# hexbot.net
KiCad netlist of a schematic drawn in Altium Designer
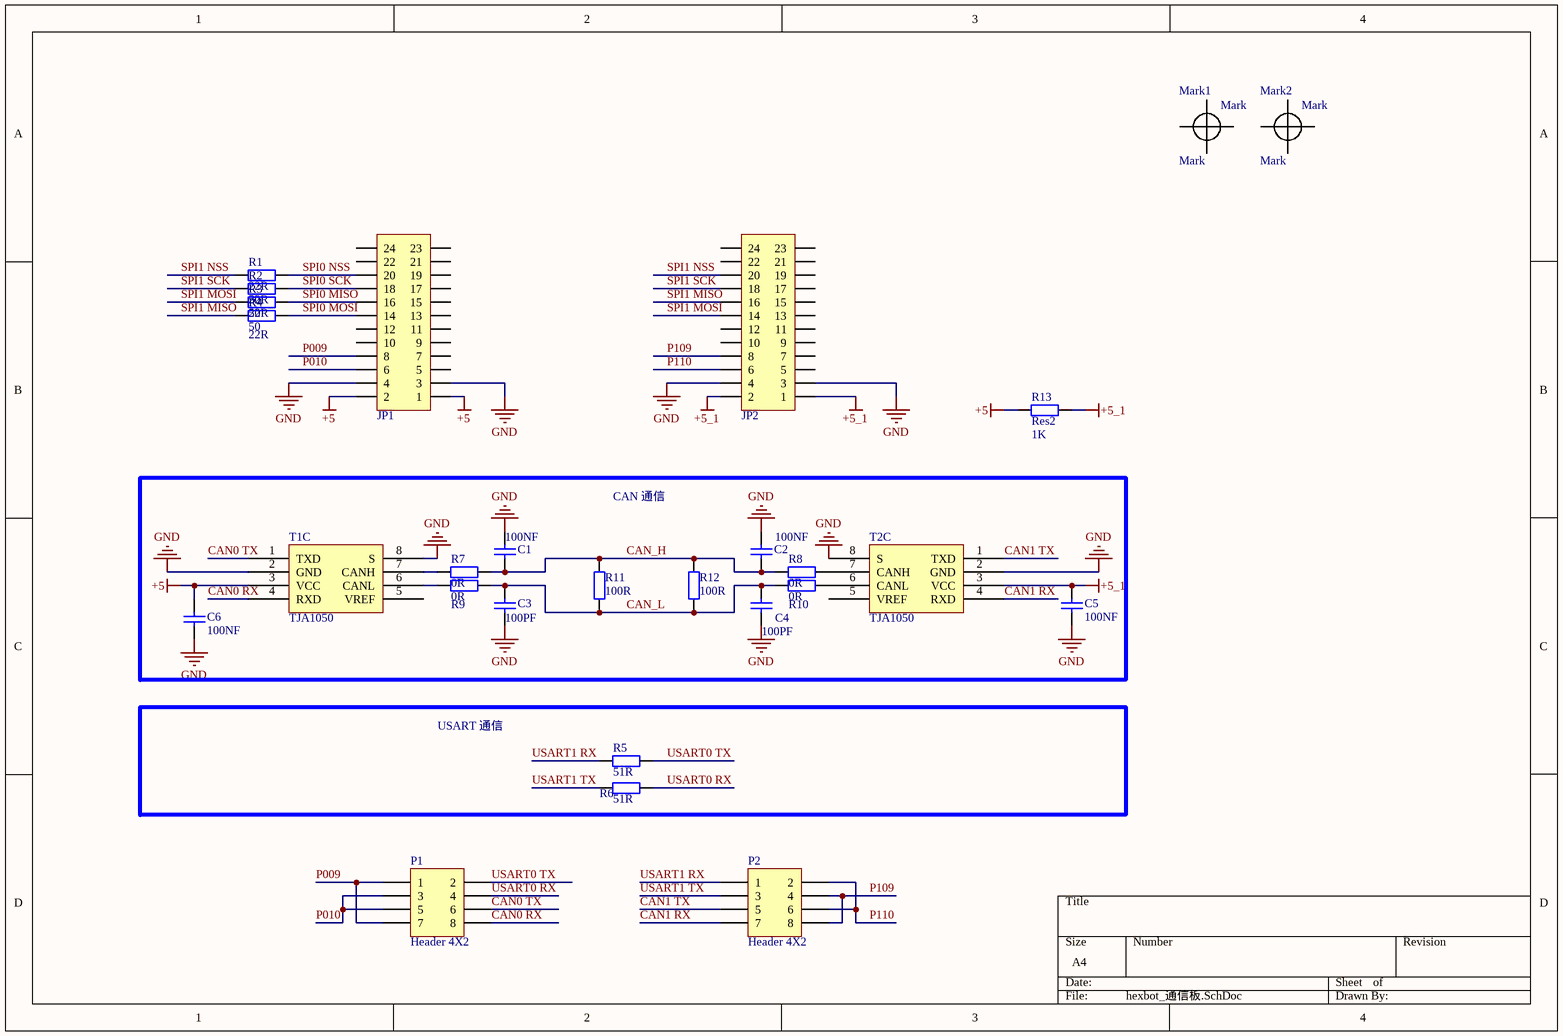
[diagram p0: hexbot_通信板.SchDoc]

(export (version "E")
  (design (tool "Eeschema 10.0.6"))
  (components
    (comp (ref "C1")
      (value "100NF")
      (footprint "1608[0603]")
      (description "Capacitor")
      (fields (field (name "PUBLISHER") "Altium Limited"))
      (libsource (lib "Miscellaneous Devices") (part "Cap"))
    )
    (comp (ref "C2")
      (value "100NF")
      (footprint "1608[0603]")
      (description "Capacitor")
      (fields (field (name "PUBLISHER") "Altium Limited"))
      (libsource (lib "Miscellaneous Devices") (part "Cap"))
    )
    (comp (ref "C3")
      (value "100PF")
      (footprint "1608[0603]")
      (description "Capacitor")
      (fields (field (name "PUBLISHER") "Altium Limited"))
      (libsource (lib "Miscellaneous Devices") (part "Cap"))
    )
    (comp (ref "C4")
      (value "100PF")
      (footprint "1608[0603]")
      (description "Capacitor")
      (fields (field (name "PUBLISHER") "Altium Limited"))
      (libsource (lib "Miscellaneous Devices") (part "Cap"))
    )
    (comp (ref "C5")
      (value "100NF")
      (footprint "1608[0603]")
      (description "Capacitor")
      (fields (field (name "PUBLISHER") "Altium Limited"))
      (libsource (lib "Miscellaneous Devices") (part "Cap"))
    )
    (comp (ref "C6")
      (value "100NF")
      (footprint "1608[0603]")
      (description "Capacitor")
      (fields (field (name "PUBLISHER") "Altium Limited"))
      (libsource (lib "Miscellaneous Devices") (part "Cap"))
    )
    (comp (ref "JP1")
      (value "Header 2X11")
      (footprint "HDR2.54-WI-2x12P")
      (description "12*2P接插件")
      (fields (field (name "版权归属") "封装库来自淘宝卖家 ID：黄晶宝石"))
      (libsource (lib "5.4 - 接插件-脚距2.54 (100mil) ") (part "Header 12X2"))
    )
    (comp (ref "JP2")
      (value "Header 2X11")
      (footprint "HDR2.54-WI-2x12P")
      (description "12*2P接插件")
      (fields (field (name "版权归属") "封装库来自淘宝卖家 ID：黄晶宝石"))
      (libsource (lib "5.4 - 接插件-脚距2.54 (100mil) ") (part "Header 12X2"))
    )
    (comp (ref "Mark1") (value "Mark") (footprint "Mark:Mark") (libsource (lib "Mark") (part "Mark")))
    (comp (ref "Mark2") (value "Mark") (footprint "Mark:Mark") (libsource (lib "Mark") (part "Mark")))
    (comp (ref "P1")
      (value "Header 4X2")
      (footprint "HDR2X4")
      (description "Header, 4-Pin, Dual row")
      (fields (field (name "PUBLISHER") "Altium Limited"))
      (libsource (lib "Miscellaneous Connectors") (part "Header 4X2"))
    )
    (comp (ref "P2")
      (value "Header 4X2")
      (footprint "HDR2X4")
      (description "Header, 4-Pin, Dual row")
      (fields (field (name "PUBLISHER") "Altium Limited"))
      (libsource (lib "Miscellaneous Connectors") (part "Header 4X2"))
    )
    (comp (ref "R1")
      (value "22R")
      (footprint "1608[0603]")
      (description "Resistor")
      (fields (field (name "ALTIUM_VALUE") "50") (field (name "PUBLISHER") "Altium Limited"))
      (libsource (lib "Miscellaneous Devices") (part "Res2"))
    )
    (comp (ref "R2")
      (value "22R")
      (footprint "1608[0603]")
      (description "Resistor")
      (fields (field (name "ALTIUM_VALUE") "50") (field (name "PUBLISHER") "Altium Limited"))
      (libsource (lib "Miscellaneous Devices") (part "Res2"))
    )
    (comp (ref "R3")
      (value "22R")
      (footprint "1608[0603]")
      (description "Resistor")
      (fields (field (name "ALTIUM_VALUE") "50") (field (name "PUBLISHER") "Altium Limited"))
      (libsource (lib "Miscellaneous Devices") (part "Res2"))
    )
    (comp (ref "R4")
      (value "22R")
      (footprint "1608[0603]")
      (description "Resistor")
      (fields (field (name "PUBLISHER") "Altium Limited"))
      (libsource (lib "Miscellaneous Devices") (part "Res2"))
    )
    (comp (ref "R5")
      (value "51R")
      (footprint "1608[0603]")
      (description "Resistor")
      (fields (field (name "PUBLISHER") "Altium Limited"))
      (libsource (lib "Miscellaneous Devices") (part "Res2"))
    )
    (comp (ref "R6")
      (value "51R")
      (footprint "1608[0603]")
      (description "Resistor")
      (fields (field (name "PUBLISHER") "Altium Limited"))
      (libsource (lib "Miscellaneous Devices") (part "Res2"))
    )
    (comp (ref "R7")
      (value "0R")
      (footprint "1608[0603]")
      (description "Resistor")
      (fields (field (name "PUBLISHER") "Altium Limited"))
      (libsource (lib "Miscellaneous Devices") (part "Res2"))
    )
    (comp (ref "R8")
      (value "0R")
      (footprint "1608[0603]")
      (description "Resistor")
      (fields (field (name "PUBLISHER") "Altium Limited"))
      (libsource (lib "Miscellaneous Devices") (part "Res2"))
    )
    (comp (ref "R9")
      (value "0R")
      (footprint "1608[0603]")
      (description "Resistor")
      (fields (field (name "PUBLISHER") "Altium Limited"))
      (libsource (lib "Miscellaneous Devices") (part "Res2"))
    )
    (comp (ref "R10")
      (value "0R")
      (footprint "1608[0603]")
      (description "Resistor")
      (fields (field (name "PUBLISHER") "Altium Limited"))
      (libsource (lib "Miscellaneous Devices") (part "Res2"))
    )
    (comp (ref "R11")
      (value "100R")
      (footprint "1608[0603]")
      (description "Resistor")
      (fields (field (name "PUBLISHER") "Altium Limited"))
      (libsource (lib "") (part "Res2_1"))
    )
    (comp (ref "R12")
      (value "100R")
      (footprint "1608[0603]")
      (description "Resistor")
      (fields (field (name "PUBLISHER") "Altium Limited"))
      (libsource (lib "") (part "Res2_1"))
    )
    (comp (ref "R13")
      (value "Res2")
      (footprint "1608[0603]")
      (description "Resistor")
      (fields (field (name "ALTIUM_VALUE") "1K") (field (name "PUBLISHER") "Altium Limited"))
      (libsource (lib "Miscellaneous Devices") (part "Res2"))
    )
    (comp (ref "T1") (value "TJA1050") (footprint "SO8_M") (libsource (lib "Schlib1") (part "TJA1050")))
    (comp (ref "T2") (value "TJA1050") (footprint "SO8_M") (libsource (lib "") (part "TJA1050_1")))
  )
  (nets
    (net (code "1") (name "+5") (class "Default")
      (node (ref "C6") (pin "2") (pinfunction "2_2") (pintype "passive"))
      (node (ref "JP1") (pin "1") (pinfunction "1_1") (pintype "passive"))
      (node (ref "JP1") (pin "2") (pinfunction "2_2") (pintype "passive"))
      (node (ref "R13") (pin "1") (pinfunction "1_1") (pintype "passive"))
      (node (ref "T1") (pin "3") (pinfunction "VCC_3") (pintype "passive"))
    )
    (net (code "2") (name "+5_1") (class "Default")
      (node (ref "C5") (pin "2") (pinfunction "2_2") (pintype "passive"))
      (node (ref "JP2") (pin "1") (pinfunction "1_1") (pintype "passive"))
      (node (ref "JP2") (pin "2") (pinfunction "2_2") (pintype "passive"))
      (node (ref "R13") (pin "2") (pinfunction "2_2") (pintype "passive"))
      (node (ref "T2") (pin "3") (pinfunction "VCC_3") (pintype "passive"))
    )
    (net (code "3") (name "/CAN0 RX") (class "Default")
      (node (ref "P1") (pin "8") (pinfunction "8_8") (pintype "passive"))
      (node (ref "T1") (pin "4") (pinfunction "RXD_4") (pintype "passive"))
    )
    (net (code "4") (name "/CAN0 TX") (class "Default")
      (node (ref "P1") (pin "6") (pinfunction "6_6") (pintype "passive"))
      (node (ref "T1") (pin "1") (pinfunction "TXD_1") (pintype "passive"))
    )
    (net (code "5") (name "/CAN1 RX") (class "Default")
      (node (ref "P2") (pin "7") (pinfunction "7_7") (pintype "passive"))
      (node (ref "T2") (pin "4") (pinfunction "RXD_4") (pintype "passive"))
    )
    (net (code "6") (name "/CAN1 TX") (class "Default")
      (node (ref "P2") (pin "5") (pinfunction "5_5") (pintype "passive"))
      (node (ref "T2") (pin "1") (pinfunction "TXD_1") (pintype "passive"))
    )
    (net (code "7") (name "/CAN_H") (class "Default")
      (node (ref "C1") (pin "1") (pinfunction "1_1") (pintype "passive"))
      (node (ref "C2") (pin "1") (pinfunction "1_1") (pintype "passive"))
      (node (ref "R11") (pin "2") (pinfunction "2_2") (pintype "passive"))
      (node (ref "R12") (pin "2") (pinfunction "2_2") (pintype "passive"))
      (node (ref "R7") (pin "2") (pinfunction "2_2") (pintype "passive"))
      (node (ref "R8") (pin "1") (pinfunction "1_1") (pintype "passive"))
    )
    (net (code "8") (name "/CAN_L") (class "Default")
      (node (ref "C3") (pin "2") (pinfunction "2_2") (pintype "passive"))
      (node (ref "C4") (pin "2") (pinfunction "2_2") (pintype "passive"))
      (node (ref "R10") (pin "1") (pinfunction "1_1") (pintype "passive"))
      (node (ref "R11") (pin "1") (pinfunction "1_1") (pintype "passive"))
      (node (ref "R12") (pin "1") (pinfunction "1_1") (pintype "passive"))
      (node (ref "R9") (pin "2") (pinfunction "2_2") (pintype "passive"))
    )
    (net (code "9") (name "/P009") (class "Default")
      (node (ref "JP1") (pin "8") (pinfunction "8_8") (pintype "passive"))
      (node (ref "P1") (pin "1") (pinfunction "1_1") (pintype "passive"))
      (node (ref "P1") (pin "7") (pinfunction "7_7") (pintype "passive"))
    )
    (net (code "10") (name "/P010") (class "Default")
      (node (ref "JP1") (pin "6") (pinfunction "6_6") (pintype "passive"))
      (node (ref "P1") (pin "3") (pinfunction "3_3") (pintype "passive"))
      (node (ref "P1") (pin "5") (pinfunction "5_5") (pintype "passive"))
    )
    (net (code "11") (name "/P109") (class "Default")
      (node (ref "JP2") (pin "8") (pinfunction "8_8") (pintype "passive"))
      (node (ref "P2") (pin "4") (pinfunction "4_4") (pintype "passive"))
      (node (ref "P2") (pin "8") (pinfunction "8_8") (pintype "passive"))
    )
    (net (code "12") (name "/P110") (class "Default")
      (node (ref "JP2") (pin "6") (pinfunction "6_6") (pintype "passive"))
      (node (ref "P2") (pin "2") (pinfunction "2_2") (pintype "passive"))
      (node (ref "P2") (pin "6") (pinfunction "6_6") (pintype "passive"))
    )
    (net (code "13") (name "/SPI0 MISO") (class "Default")
      (node (ref "JP1") (pin "16") (pinfunction "16_16") (pintype "passive"))
      (node (ref "R3") (pin "2") (pinfunction "2_2") (pintype "passive"))
    )
    (net (code "14") (name "/SPI0 MOSI") (class "Default")
      (node (ref "JP1") (pin "14") (pinfunction "14_14") (pintype "passive"))
      (node (ref "R4") (pin "2") (pinfunction "2_2") (pintype "passive"))
    )
    (net (code "15") (name "/SPI0 NSS") (class "Default")
      (node (ref "JP1") (pin "20") (pinfunction "20_20") (pintype "passive"))
      (node (ref "R1") (pin "2") (pinfunction "2_2") (pintype "passive"))
    )
    (net (code "16") (name "/SPI0 SCK") (class "Default")
      (node (ref "JP1") (pin "18") (pinfunction "18_18") (pintype "passive"))
      (node (ref "R2") (pin "2") (pinfunction "2_2") (pintype "passive"))
    )
    (net (code "17") (name "/SPI1 MISO") (class "Default")
      (node (ref "JP2") (pin "16") (pinfunction "16_16") (pintype "passive"))
      (node (ref "R4") (pin "1") (pinfunction "1_1") (pintype "passive"))
    )
    (net (code "18") (name "/SPI1 MOSI") (class "Default")
      (node (ref "JP2") (pin "14") (pinfunction "14_14") (pintype "passive"))
      (node (ref "R3") (pin "1") (pinfunction "1_1") (pintype "passive"))
    )
    (net (code "19") (name "/SPI1 NSS") (class "Default")
      (node (ref "JP2") (pin "20") (pinfunction "20_20") (pintype "passive"))
      (node (ref "R1") (pin "1") (pinfunction "1_1") (pintype "passive"))
    )
    (net (code "20") (name "/SPI1 SCK") (class "Default")
      (node (ref "JP2") (pin "18") (pinfunction "18_18") (pintype "passive"))
      (node (ref "R2") (pin "1") (pinfunction "1_1") (pintype "passive"))
    )
    (net (code "21") (name "/USART0 RX") (class "Default")
      (node (ref "P1") (pin "4") (pinfunction "4_4") (pintype "passive"))
      (node (ref "R6") (pin "2") (pinfunction "2_2") (pintype "passive"))
    )
    (net (code "22") (name "/USART0 TX") (class "Default")
      (node (ref "P1") (pin "2") (pinfunction "2_2") (pintype "passive"))
      (node (ref "R5") (pin "2") (pinfunction "2_2") (pintype "passive"))
    )
    (net (code "23") (name "/USART1 RX") (class "Default")
      (node (ref "P2") (pin "1") (pinfunction "1_1") (pintype "passive"))
      (node (ref "R5") (pin "1") (pinfunction "1_1") (pintype "passive"))
    )
    (net (code "24") (name "/USART1 TX") (class "Default")
      (node (ref "P2") (pin "3") (pinfunction "3_3") (pintype "passive"))
      (node (ref "R6") (pin "1") (pinfunction "1_1") (pintype "passive"))
    )
    (net (code "25") (name "GND") (class "Default")
      (node (ref "C1") (pin "2") (pinfunction "2_2") (pintype "passive"))
      (node (ref "C2") (pin "2") (pinfunction "2_2") (pintype "passive"))
      (node (ref "C3") (pin "1") (pinfunction "1_1") (pintype "passive"))
      (node (ref "C4") (pin "1") (pinfunction "1_1") (pintype "passive"))
      (node (ref "C5") (pin "1") (pinfunction "1_1") (pintype "passive"))
      (node (ref "C6") (pin "1") (pinfunction "1_1") (pintype "passive"))
      (node (ref "JP1") (pin "3") (pinfunction "3_3") (pintype "passive"))
      (node (ref "JP1") (pin "4") (pinfunction "4_4") (pintype "passive"))
      (node (ref "JP2") (pin "3") (pinfunction "3_3") (pintype "passive"))
      (node (ref "JP2") (pin "4") (pinfunction "4_4") (pintype "passive"))
      (node (ref "T1") (pin "2") (pinfunction "GND_2") (pintype "passive"))
      (node (ref "T1") (pin "8") (pinfunction "S_8") (pintype "passive"))
      (node (ref "T2") (pin "2") (pinfunction "GND_2") (pintype "passive"))
      (node (ref "T2") (pin "8") (pinfunction "S_8") (pintype "passive"))
    )
    (net (code "26") (name "Net-(T1C-CANH)") (class "Default")
      (node (ref "R7") (pin "1") (pinfunction "1_1") (pintype "passive"))
      (node (ref "T1") (pin "7") (pinfunction "CANH_7") (pintype "passive"))
    )
    (net (code "27") (name "Net-(T1C-CANL)") (class "Default")
      (node (ref "R9") (pin "1") (pinfunction "1_1") (pintype "passive"))
      (node (ref "T1") (pin "6") (pinfunction "CANL_6") (pintype "passive"))
    )
    (net (code "28") (name "Net-(T2C-CANH)") (class "Default")
      (node (ref "R8") (pin "2") (pinfunction "2_2") (pintype "passive"))
      (node (ref "T2") (pin "7") (pinfunction "CANH_7") (pintype "passive"))
    )
    (net (code "29") (name "Net-(T2C-CANL)") (class "Default")
      (node (ref "R10") (pin "2") (pinfunction "2_2") (pintype "passive"))
      (node (ref "T2") (pin "6") (pinfunction "CANL_6") (pintype "passive"))
    )
    (net (code "30") (name "unconnected-(JP1-Pad5)") (class "Default")
      (node (ref "JP1") (pin "5") (pinfunction "5_5") (pintype "passive"))
    )
    (net (code "31") (name "unconnected-(JP1-Pad7)") (class "Default")
      (node (ref "JP1") (pin "7") (pinfunction "7_7") (pintype "passive"))
    )
    (net (code "32") (name "unconnected-(JP1-Pad9)") (class "Default")
      (node (ref "JP1") (pin "9") (pinfunction "9_9") (pintype "passive"))
    )
    (net (code "33") (name "unconnected-(JP1-Pad10)") (class "Default")
      (node (ref "JP1") (pin "10") (pinfunction "10_10") (pintype "passive"))
    )
    (net (code "34") (name "unconnected-(JP1-Pad11)") (class "Default")
      (node (ref "JP1") (pin "11") (pinfunction "11_11") (pintype "passive"))
    )
    (net (code "35") (name "unconnected-(JP1-Pad12)") (class "Default")
      (node (ref "JP1") (pin "12") (pinfunction "12_12") (pintype "passive"))
    )
    (net (code "36") (name "unconnected-(JP1-Pad13)") (class "Default")
      (node (ref "JP1") (pin "13") (pinfunction "13_13") (pintype "passive"))
    )
    (net (code "37") (name "unconnected-(JP1-Pad15)") (class "Default")
      (node (ref "JP1") (pin "15") (pinfunction "15_15") (pintype "passive"))
    )
    (net (code "38") (name "unconnected-(JP1-Pad17)") (class "Default")
      (node (ref "JP1") (pin "17") (pinfunction "17_17") (pintype "passive"))
    )
    (net (code "39") (name "unconnected-(JP1-Pad19)") (class "Default")
      (node (ref "JP1") (pin "19") (pinfunction "19_19") (pintype "passive"))
    )
    (net (code "40") (name "unconnected-(JP1-Pad21)") (class "Default")
      (node (ref "JP1") (pin "21") (pinfunction "21_21") (pintype "passive"))
    )
    (net (code "41") (name "unconnected-(JP1-Pad22)") (class "Default")
      (node (ref "JP1") (pin "22") (pinfunction "22_22") (pintype "passive"))
    )
    (net (code "42") (name "unconnected-(JP1-Pad23)") (class "Default")
      (node (ref "JP1") (pin "23") (pinfunction "23_23") (pintype "passive"))
    )
    (net (code "43") (name "unconnected-(JP1-Pad24)") (class "Default")
      (node (ref "JP1") (pin "24") (pinfunction "24_24") (pintype "passive"))
    )
    (net (code "44") (name "unconnected-(JP2-Pad5)") (class "Default")
      (node (ref "JP2") (pin "5") (pinfunction "5_5") (pintype "passive"))
    )
    (net (code "45") (name "unconnected-(JP2-Pad7)") (class "Default")
      (node (ref "JP2") (pin "7") (pinfunction "7_7") (pintype "passive"))
    )
    (net (code "46") (name "unconnected-(JP2-Pad9)") (class "Default")
      (node (ref "JP2") (pin "9") (pinfunction "9_9") (pintype "passive"))
    )
    (net (code "47") (name "unconnected-(JP2-Pad10)") (class "Default")
      (node (ref "JP2") (pin "10") (pinfunction "10_10") (pintype "passive"))
    )
    (net (code "48") (name "unconnected-(JP2-Pad11)") (class "Default")
      (node (ref "JP2") (pin "11") (pinfunction "11_11") (pintype "passive"))
    )
    (net (code "49") (name "unconnected-(JP2-Pad12)") (class "Default")
      (node (ref "JP2") (pin "12") (pinfunction "12_12") (pintype "passive"))
    )
    (net (code "50") (name "unconnected-(JP2-Pad13)") (class "Default")
      (node (ref "JP2") (pin "13") (pinfunction "13_13") (pintype "passive"))
    )
    (net (code "51") (name "unconnected-(JP2-Pad15)") (class "Default")
      (node (ref "JP2") (pin "15") (pinfunction "15_15") (pintype "passive"))
    )
    (net (code "52") (name "unconnected-(JP2-Pad17)") (class "Default")
      (node (ref "JP2") (pin "17") (pinfunction "17_17") (pintype "passive"))
    )
    (net (code "53") (name "unconnected-(JP2-Pad19)") (class "Default")
      (node (ref "JP2") (pin "19") (pinfunction "19_19") (pintype "passive"))
    )
    (net (code "54") (name "unconnected-(JP2-Pad21)") (class "Default")
      (node (ref "JP2") (pin "21") (pinfunction "21_21") (pintype "passive"))
    )
    (net (code "55") (name "unconnected-(JP2-Pad22)") (class "Default")
      (node (ref "JP2") (pin "22") (pinfunction "22_22") (pintype "passive"))
    )
    (net (code "56") (name "unconnected-(JP2-Pad23)") (class "Default")
      (node (ref "JP2") (pin "23") (pinfunction "23_23") (pintype "passive"))
    )
    (net (code "57") (name "unconnected-(JP2-Pad24)") (class "Default")
      (node (ref "JP2") (pin "24") (pinfunction "24_24") (pintype "passive"))
    )
    (net (code "58") (name "unconnected-(T1C-VREF-Pad5)") (class "Default")
      (node (ref "T1") (pin "5") (pinfunction "VREF_5") (pintype "passive"))
    )
    (net (code "59") (name "unconnected-(T2C-VREF-Pad5)") (class "Default")
      (node (ref "T2") (pin "5") (pinfunction "VREF_5") (pintype "passive"))
    )
  )
)
